# mimic1568.net
KiCad netlist of a schematic drawn in EAGLE
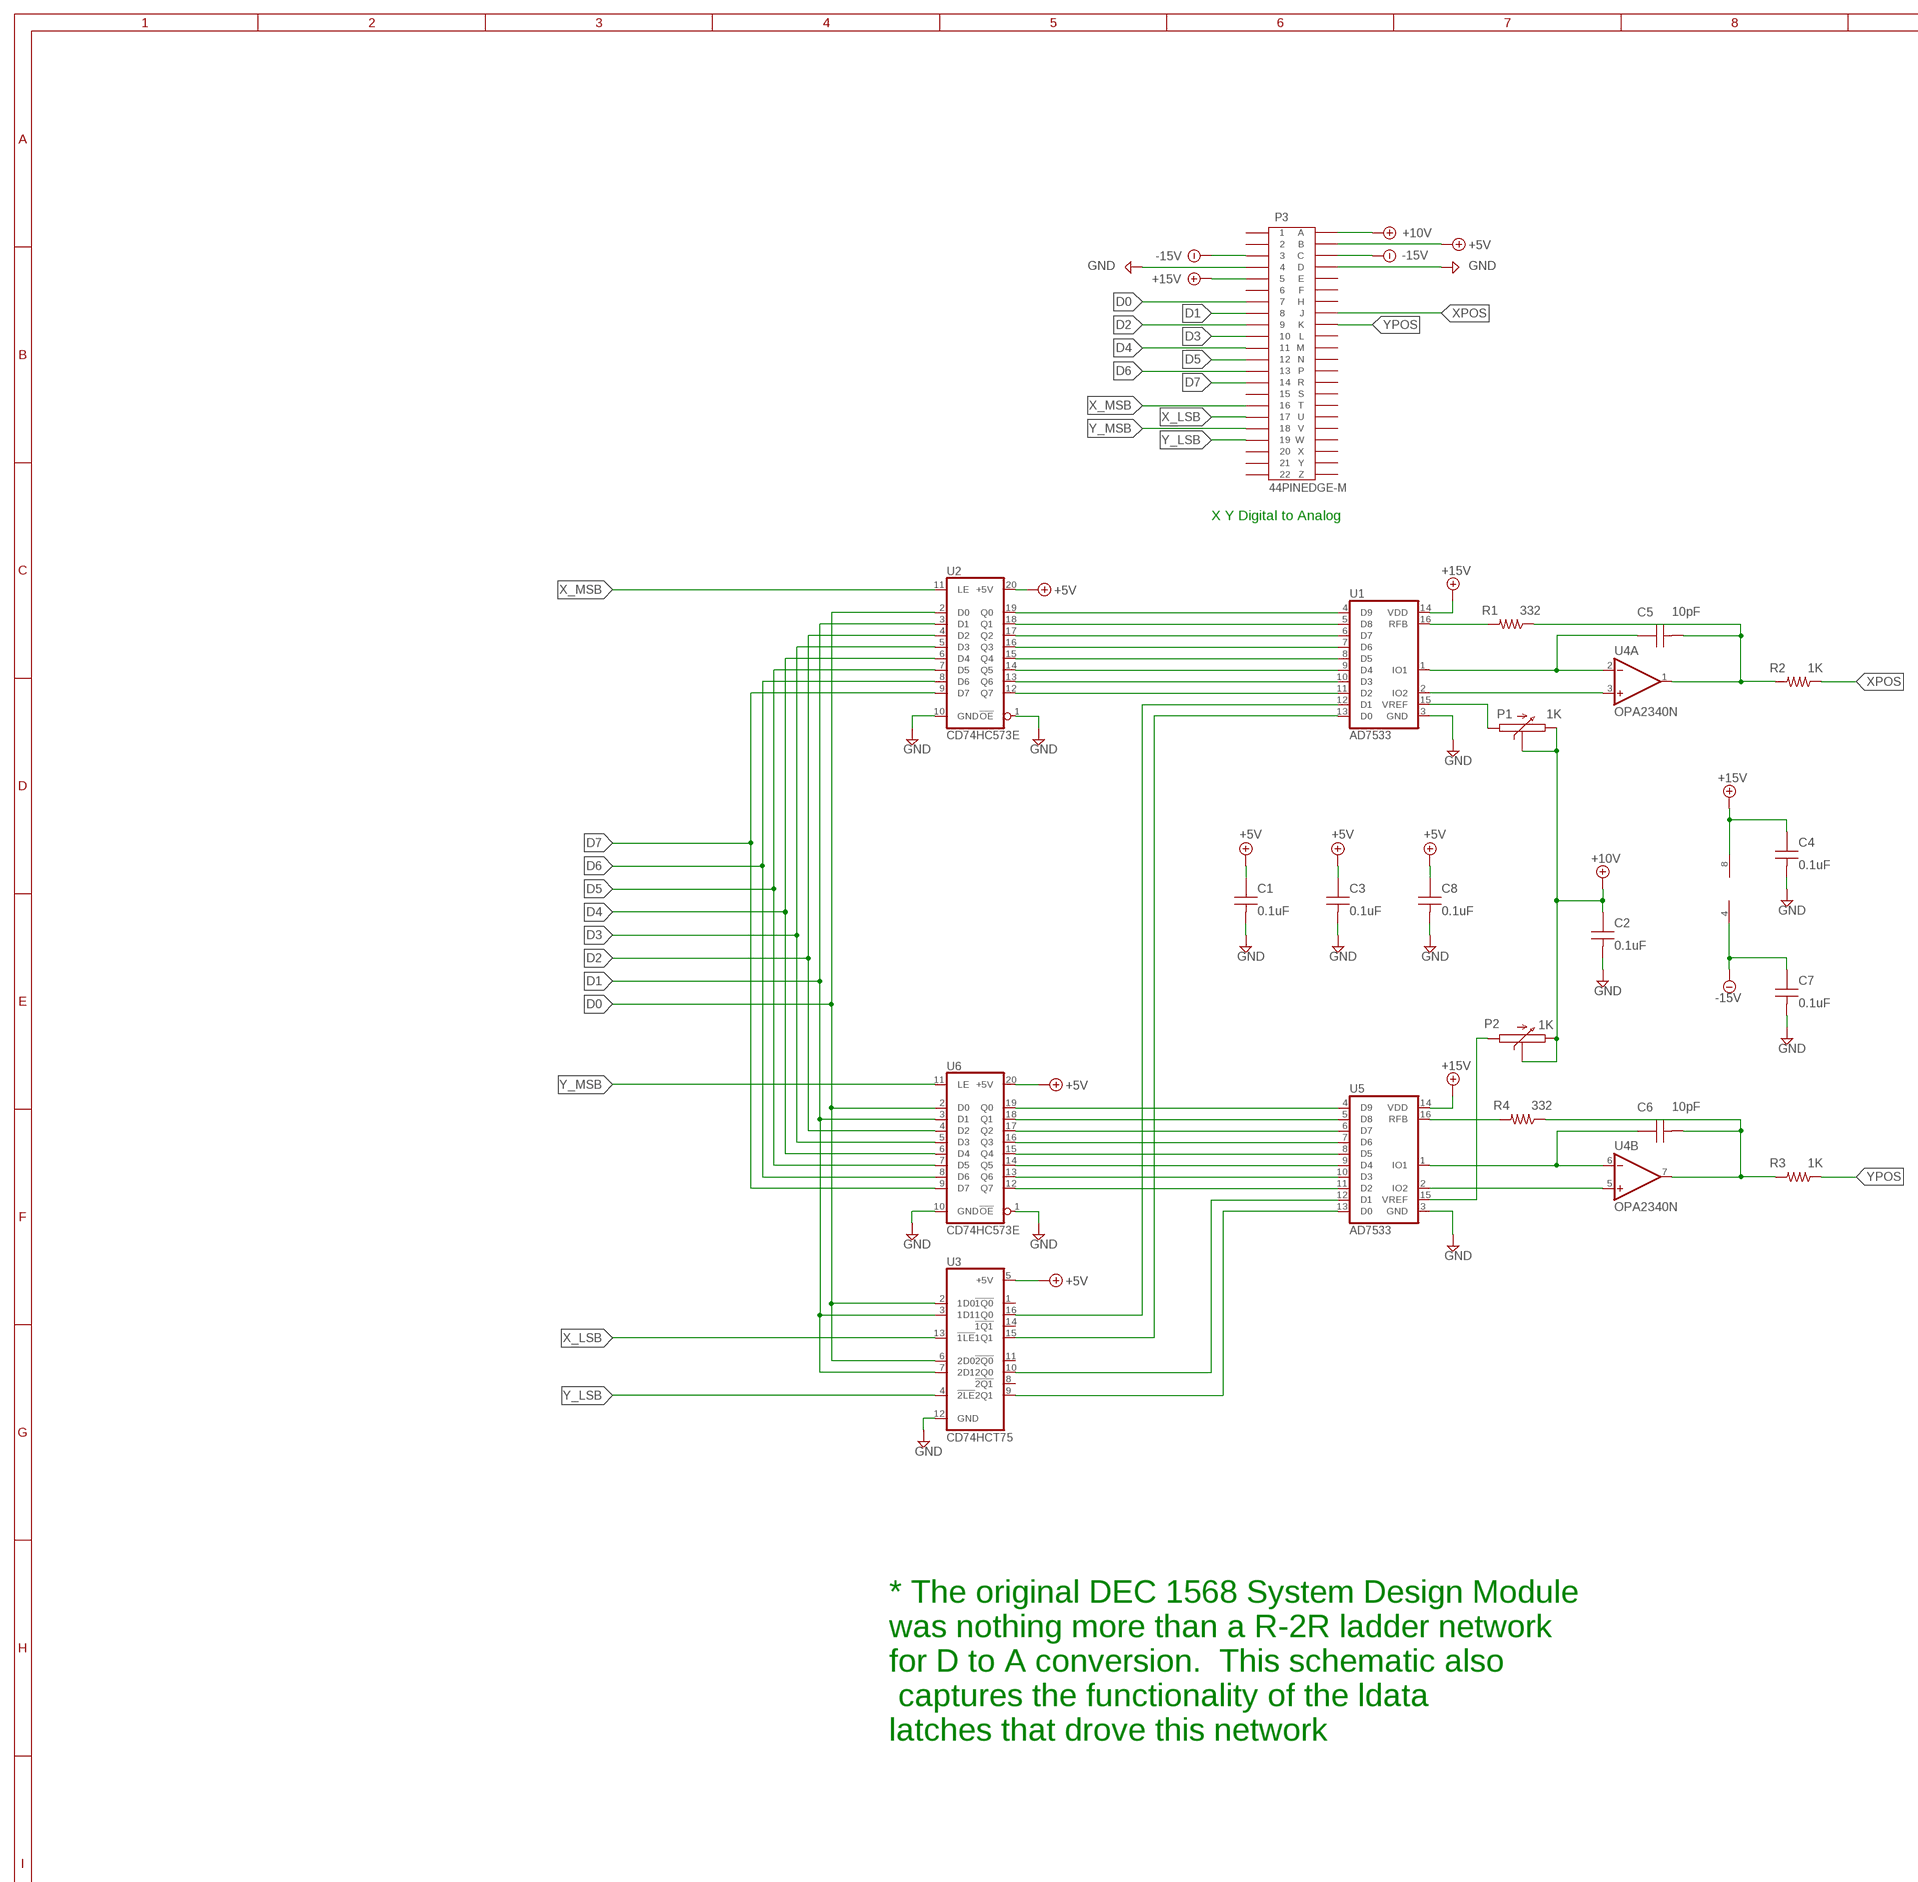
[diagram p0: schematic, sheet 1, part 1 of 2]
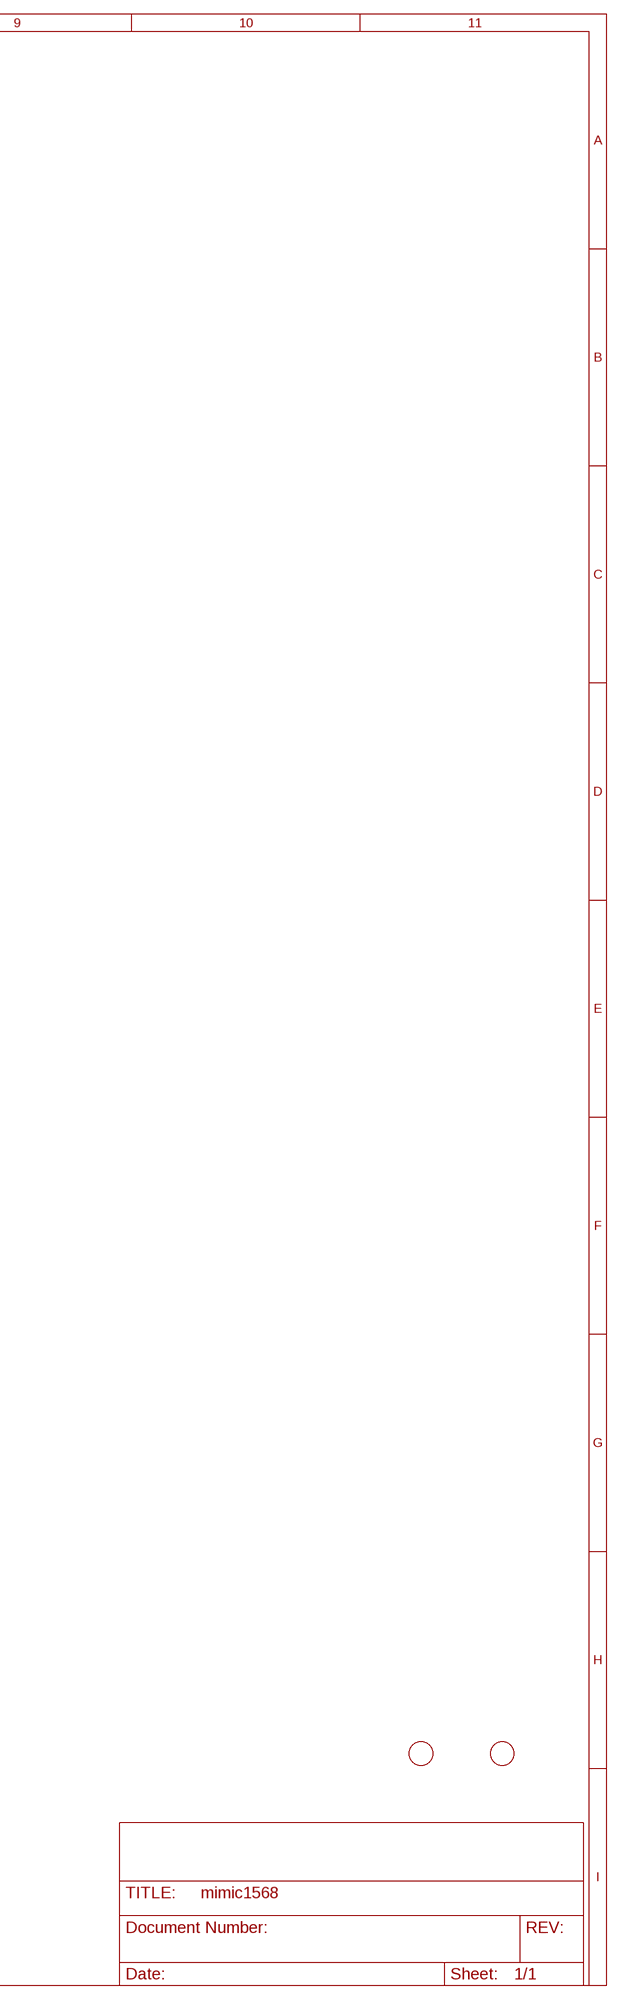
[diagram p1: schematic, sheet 1, part 2 of 2]

(export (version "E")
  (design (tool "Eeschema 10.0.6"))
  (components
    (comp (ref "C1")
      (value "0.1uF")
      (footprint "eagle-import:5MM_TH")
      (fields (field (name "MPN") "FA26X8R2A104KNU06"))
      (libsource (lib "eagle-import") (part "CAP0.1UF100V"))
    )
    (comp (ref "C2")
      (value "0.1uF")
      (footprint "eagle-import:5MM_TH")
      (fields (field (name "MPN") "FA26X8R2A104KNU06"))
      (libsource (lib "eagle-import") (part "CAP0.1UF100V"))
    )
    (comp (ref "C3")
      (value "0.1uF")
      (footprint "eagle-import:5MM_TH")
      (fields (field (name "MPN") "FA26X8R2A104KNU06"))
      (libsource (lib "eagle-import") (part "CAP0.1UF100V"))
    )
    (comp (ref "C4")
      (value "0.1uF")
      (footprint "eagle-import:5MM_TH")
      (fields (field (name "MPN") "FA26X8R2A104KNU06"))
      (libsource (lib "eagle-import") (part "CAP0.1UF100V"))
    )
    (comp (ref "C5")
      (value "10pF")
      (footprint "eagle-import:5MM_TH")
      (fields (field (name "MPN") "FA26X8R2A104KNU06"))
      (libsource (lib "eagle-import") (part "CAP0.1UF100V"))
    )
    (comp (ref "C6")
      (value "10pF")
      (footprint "eagle-import:5MM_TH")
      (fields (field (name "MPN") "FA26X8R2A104KNU06"))
      (libsource (lib "eagle-import") (part "CAP0.1UF100V"))
    )
    (comp (ref "C7")
      (value "0.1uF")
      (footprint "eagle-import:5MM_TH")
      (fields (field (name "MPN") "FA26X8R2A104KNU06"))
      (libsource (lib "eagle-import") (part "CAP0.1UF100V"))
    )
    (comp (ref "C8")
      (value "0.1uF")
      (footprint "eagle-import:5MM_TH")
      (fields (field (name "MPN") "FA26X8R2A104KNU06"))
      (libsource (lib "eagle-import") (part "CAP0.1UF100V"))
    )
    (comp (ref "P1")
      (value "1K")
      (footprint "eagle-import:3006P")
      (libsource (lib "eagle-import") (part "POT-3006P"))
    )
    (comp (ref "P2")
      (value "1K")
      (footprint "eagle-import:3006P")
      (libsource (lib "eagle-import") (part "POT-3006P"))
    )
    (comp (ref "P3")
      (value "44PINEDGE-M")
      (footprint "eagle-import:44PINEDGE")
      (libsource (lib "eagle-import") (part "44PINEDGE-M"))
    )
    (comp (ref "R1")
      (value "332")
      (footprint "eagle-import:0207_10")
      (libsource (lib "eagle-import") (part "R-1/4WATT"))
    )
    (comp (ref "R2")
      (value "1K")
      (footprint "eagle-import:0207_10")
      (libsource (lib "eagle-import") (part "R-1/4WATT"))
    )
    (comp (ref "R3")
      (value "1K")
      (footprint "eagle-import:0207_10")
      (libsource (lib "eagle-import") (part "R-1/4WATT"))
    )
    (comp (ref "R4")
      (value "332")
      (footprint "eagle-import:0207_10")
      (libsource (lib "eagle-import") (part "R-1/4WATT"))
    )
    (comp (ref "U$1")
      (value "FIDUCIAL")
      (footprint "eagle-import:FIDUCIAL_1MM")
      (libsource (lib "eagle-import") (part "FIDUCIAL"))
    )
    (comp (ref "U$2")
      (value "FIDUCIAL")
      (footprint "eagle-import:FIDUCIAL_1MM")
      (libsource (lib "eagle-import") (part "FIDUCIAL"))
    )
    (comp (ref "U1")
      (value "AD7533")
      (footprint "eagle-import:DIP-16")
      (libsource (lib "eagle-import") (part "AD7533"))
    )
    (comp (ref "U2")
      (value "CD74HC573E")
      (footprint "eagle-import:DIP-20")
      (libsource (lib "eagle-import") (part "CD74HC573E"))
    )
    (comp (ref "U3")
      (value "CD74HCT75")
      (footprint "eagle-import:DIP-16")
      (libsource (lib "eagle-import") (part "CD74HCT75"))
    )
    (comp (ref "U4")
      (value "OPA2340N")
      (footprint "eagle-import:DIP-08")
      (libsource (lib "eagle-import") (part "OPA2340N"))
    )
    (comp (ref "U5")
      (value "AD7533")
      (footprint "eagle-import:DIP-16")
      (libsource (lib "eagle-import") (part "AD7533"))
    )
    (comp (ref "U6")
      (value "CD74HC573E")
      (footprint "eagle-import:DIP-20")
      (libsource (lib "eagle-import") (part "CD74HC573E"))
    )
  )
  (nets
    (net (code "1") (name "+5V") (class "Default")
      (node (ref "C1") (pin "1") (pinfunction "1_1") (pintype "passive"))
      (node (ref "C3") (pin "1") (pinfunction "1_1") (pintype "passive"))
      (node (ref "C8") (pin "1") (pinfunction "1_1") (pintype "passive"))
      (node (ref "P3") (pin "B") (pinfunction "B_B") (pintype "passive"))
      (node (ref "U2") (pin "20") (pinfunction "+5V_20") (pintype "power_in"))
      (node (ref "U3") (pin "5") (pinfunction "+5V_5") (pintype "power_in"))
      (node (ref "U6") (pin "20") (pinfunction "+5V_20") (pintype "power_in"))
    )
    (net (code "2") (name "+10V") (class "Default")
      (node (ref "C2") (pin "1") (pinfunction "1_1") (pintype "passive"))
      (node (ref "P1") (pin "2") (pinfunction "2_2") (pintype "passive"))
      (node (ref "P1") (pin "3") (pinfunction "3_3") (pintype "passive"))
      (node (ref "P2") (pin "2") (pinfunction "2_2") (pintype "passive"))
      (node (ref "P2") (pin "3") (pinfunction "3_3") (pintype "passive"))
      (node (ref "P3") (pin "A") (pinfunction "A_A") (pintype "passive"))
    )
    (net (code "3") (name "+15V") (class "Default")
      (node (ref "C4") (pin "1") (pinfunction "1_1") (pintype "passive"))
      (node (ref "P3") (pin "5") (pinfunction "5_5") (pintype "passive"))
      (node (ref "U1") (pin "14") (pinfunction "VDD_14") (pintype "power_in"))
      (node (ref "U4") (pin "8") (pinfunction "V+_8") (pintype "power_in"))
      (node (ref "U5") (pin "14") (pinfunction "VDD_14") (pintype "power_in"))
    )
    (net (code "4") (name "-15V") (class "Default")
      (node (ref "C7") (pin "1") (pinfunction "1_1") (pintype "passive"))
      (node (ref "P3") (pin "3") (pinfunction "3_3") (pintype "passive"))
      (node (ref "P3") (pin "C") (pinfunction "C_C") (pintype "passive"))
      (node (ref "U4") (pin "4") (pinfunction "V-_4") (pintype "power_in"))
    )
    (net (code "5") (name "D0") (class "Default")
      (node (ref "P3") (pin "7") (pinfunction "7_7") (pintype "passive"))
      (node (ref "U2") (pin "2") (pinfunction "D0_2") (pintype "input"))
      (node (ref "U3") (pin "2") (pinfunction "1D0_2") (pintype "input"))
      (node (ref "U3") (pin "6") (pinfunction "2D0_6") (pintype "input"))
      (node (ref "U6") (pin "2") (pinfunction "D0_2") (pintype "input"))
    )
    (net (code "6") (name "D1") (class "Default")
      (node (ref "P3") (pin "8") (pinfunction "8_8") (pintype "passive"))
      (node (ref "U2") (pin "3") (pinfunction "D1_3") (pintype "input"))
      (node (ref "U3") (pin "3") (pinfunction "1D1_3") (pintype "input"))
      (node (ref "U3") (pin "7") (pinfunction "2D1_7") (pintype "input"))
      (node (ref "U6") (pin "3") (pinfunction "D1_3") (pintype "input"))
    )
    (net (code "7") (name "D2") (class "Default")
      (node (ref "P3") (pin "9") (pinfunction "9_9") (pintype "passive"))
      (node (ref "U2") (pin "4") (pinfunction "D2_4") (pintype "input"))
      (node (ref "U6") (pin "4") (pinfunction "D2_4") (pintype "input"))
    )
    (net (code "8") (name "D3") (class "Default")
      (node (ref "P3") (pin "10") (pinfunction "10_10") (pintype "passive"))
      (node (ref "U2") (pin "5") (pinfunction "D3_5") (pintype "input"))
      (node (ref "U6") (pin "5") (pinfunction "D3_5") (pintype "input"))
    )
    (net (code "9") (name "D4") (class "Default")
      (node (ref "P3") (pin "11") (pinfunction "11_11") (pintype "passive"))
      (node (ref "U2") (pin "6") (pinfunction "D4_6") (pintype "input"))
      (node (ref "U6") (pin "6") (pinfunction "D4_6") (pintype "input"))
    )
    (net (code "10") (name "D5") (class "Default")
      (node (ref "P3") (pin "12") (pinfunction "12_12") (pintype "passive"))
      (node (ref "U2") (pin "7") (pinfunction "D5_7") (pintype "input"))
      (node (ref "U6") (pin "7") (pinfunction "D5_7") (pintype "input"))
    )
    (net (code "11") (name "D6") (class "Default")
      (node (ref "P3") (pin "13") (pinfunction "13_13") (pintype "passive"))
      (node (ref "U2") (pin "8") (pinfunction "D6_8") (pintype "input"))
      (node (ref "U6") (pin "8") (pinfunction "D6_8") (pintype "input"))
    )
    (net (code "12") (name "D7") (class "Default")
      (node (ref "P3") (pin "14") (pinfunction "14_14") (pintype "passive"))
      (node (ref "U2") (pin "9") (pinfunction "D7_9") (pintype "input"))
      (node (ref "U6") (pin "9") (pinfunction "D7_9") (pintype "input"))
    )
    (net (code "13") (name "GND") (class "Default")
      (node (ref "C1") (pin "2") (pinfunction "2_2") (pintype "passive"))
      (node (ref "C2") (pin "2") (pinfunction "2_2") (pintype "passive"))
      (node (ref "C3") (pin "2") (pinfunction "2_2") (pintype "passive"))
      (node (ref "C4") (pin "2") (pinfunction "2_2") (pintype "passive"))
      (node (ref "C7") (pin "2") (pinfunction "2_2") (pintype "passive"))
      (node (ref "C8") (pin "2") (pinfunction "2_2") (pintype "passive"))
      (node (ref "P3") (pin "4") (pinfunction "4_4") (pintype "passive"))
      (node (ref "P3") (pin "D") (pinfunction "D_D") (pintype "passive"))
      (node (ref "U1") (pin "3") (pinfunction "GND_3") (pintype "power_in"))
      (node (ref "U2") (pin "1") (pinfunction "~{OE}_1") (pintype "input"))
      (node (ref "U2") (pin "10") (pinfunction "GND_10") (pintype "power_in"))
      (node (ref "U3") (pin "12") (pinfunction "GND_12") (pintype "power_in"))
      (node (ref "U5") (pin "3") (pinfunction "GND_3") (pintype "power_in"))
      (node (ref "U6") (pin "1") (pinfunction "~{OE}_1") (pintype "input"))
      (node (ref "U6") (pin "10") (pinfunction "GND_10") (pintype "power_in"))
    )
    (net (code "14") (name "Net-(R1-P$1)") (class "Default")
      (node (ref "C5") (pin "2") (pinfunction "2_2") (pintype "passive"))
      (node (ref "R1") (pin "1") (pinfunction "P$1_1") (pintype "passive"))
      (node (ref "R2") (pin "2") (pinfunction "P$2_2") (pintype "passive"))
      (node (ref "U4") (pin "1") (pinfunction "OUT_1") (pintype "output"))
    )
    (net (code "15") (name "Net-(R1-P$2)") (class "Default")
      (node (ref "R1") (pin "2") (pinfunction "P$2_2") (pintype "passive"))
      (node (ref "U1") (pin "16") (pinfunction "RFB_16") (pintype "input"))
    )
    (net (code "16") (name "Net-(R3-P$2)") (class "Default")
      (node (ref "C6") (pin "2") (pinfunction "2_2") (pintype "passive"))
      (node (ref "R3") (pin "2") (pinfunction "P$2_2") (pintype "passive"))
      (node (ref "R4") (pin "1") (pinfunction "P$1_1") (pintype "passive"))
      (node (ref "U4") (pin "7") (pinfunction "OUT_7") (pintype "output"))
    )
    (net (code "17") (name "Net-(R4-P$2)") (class "Default")
      (node (ref "R4") (pin "2") (pinfunction "P$2_2") (pintype "passive"))
      (node (ref "U5") (pin "16") (pinfunction "RFB_16") (pintype "input"))
    )
    (net (code "18") (name "Net-(U1-D0)") (class "Default")
      (node (ref "U1") (pin "13") (pinfunction "D0_13") (pintype "input"))
      (node (ref "U3") (pin "15") (pinfunction "1Q1_15") (pintype "output"))
    )
    (net (code "19") (name "Net-(U1-D1)") (class "Default")
      (node (ref "U1") (pin "12") (pinfunction "D1_12") (pintype "input"))
      (node (ref "U3") (pin "16") (pinfunction "1Q0_16") (pintype "output"))
    )
    (net (code "20") (name "Net-(U1-D2)") (class "Default")
      (node (ref "U1") (pin "11") (pinfunction "D2_11") (pintype "input"))
      (node (ref "U2") (pin "12") (pinfunction "Q7_12") (pintype "tri_state"))
    )
    (net (code "21") (name "Net-(U1-D3)") (class "Default")
      (node (ref "U1") (pin "10") (pinfunction "D3_10") (pintype "input"))
      (node (ref "U2") (pin "13") (pinfunction "Q6_13") (pintype "tri_state"))
    )
    (net (code "22") (name "Net-(U1-D4)") (class "Default")
      (node (ref "U1") (pin "9") (pinfunction "D4_9") (pintype "input"))
      (node (ref "U2") (pin "14") (pinfunction "Q5_14") (pintype "tri_state"))
    )
    (net (code "23") (name "Net-(U1-D5)") (class "Default")
      (node (ref "U1") (pin "8") (pinfunction "D5_8") (pintype "input"))
      (node (ref "U2") (pin "15") (pinfunction "Q4_15") (pintype "tri_state"))
    )
    (net (code "24") (name "Net-(U1-D6)") (class "Default")
      (node (ref "U1") (pin "7") (pinfunction "D6_7") (pintype "input"))
      (node (ref "U2") (pin "16") (pinfunction "Q3_16") (pintype "tri_state"))
    )
    (net (code "25") (name "Net-(U1-D7)") (class "Default")
      (node (ref "U1") (pin "6") (pinfunction "D7_6") (pintype "input"))
      (node (ref "U2") (pin "17") (pinfunction "Q2_17") (pintype "tri_state"))
    )
    (net (code "26") (name "Net-(U1-D8)") (class "Default")
      (node (ref "U1") (pin "5") (pinfunction "D8_5") (pintype "input"))
      (node (ref "U2") (pin "18") (pinfunction "Q1_18") (pintype "tri_state"))
    )
    (net (code "27") (name "Net-(U1-D9)") (class "Default")
      (node (ref "U1") (pin "4") (pinfunction "D9_4") (pintype "input"))
      (node (ref "U2") (pin "19") (pinfunction "Q0_19") (pintype "tri_state"))
    )
    (net (code "28") (name "Net-(U1-IO1)") (class "Default")
      (node (ref "C5") (pin "1") (pinfunction "1_1") (pintype "passive"))
      (node (ref "U1") (pin "1") (pinfunction "IO1_1") (pintype "output"))
      (node (ref "U4") (pin "2") (pinfunction "-IN_2") (pintype "input"))
    )
    (net (code "29") (name "Net-(U1-IO2)") (class "Default")
      (node (ref "U1") (pin "2") (pinfunction "IO2_2") (pintype "output"))
      (node (ref "U4") (pin "3") (pinfunction "+IN_3") (pintype "input"))
    )
    (net (code "30") (name "Net-(U1-VREF)") (class "Default")
      (node (ref "P1") (pin "1") (pinfunction "1_1") (pintype "passive"))
      (node (ref "U1") (pin "15") (pinfunction "VREF_15") (pintype "power_in"))
    )
    (net (code "31") (name "Net-(U3-2Q0)") (class "Default")
      (node (ref "U3") (pin "10") (pinfunction "2Q0_10") (pintype "output"))
      (node (ref "U5") (pin "12") (pinfunction "D1_12") (pintype "input"))
    )
    (net (code "32") (name "Net-(U3-2Q1)") (class "Default")
      (node (ref "U3") (pin "9") (pinfunction "2Q1_9") (pintype "output"))
      (node (ref "U5") (pin "13") (pinfunction "D0_13") (pintype "input"))
    )
    (net (code "33") (name "Net-(U4B-+IN)") (class "Default")
      (node (ref "U4") (pin "5") (pinfunction "+IN_5") (pintype "input"))
      (node (ref "U5") (pin "2") (pinfunction "IO2_2") (pintype "output"))
    )
    (net (code "34") (name "Net-(U4B--IN)") (class "Default")
      (node (ref "C6") (pin "1") (pinfunction "1_1") (pintype "passive"))
      (node (ref "U4") (pin "6") (pinfunction "-IN_6") (pintype "input"))
      (node (ref "U5") (pin "1") (pinfunction "IO1_1") (pintype "output"))
    )
    (net (code "35") (name "Net-(U5-D2)") (class "Default")
      (node (ref "U5") (pin "11") (pinfunction "D2_11") (pintype "input"))
      (node (ref "U6") (pin "12") (pinfunction "Q7_12") (pintype "tri_state"))
    )
    (net (code "36") (name "Net-(U5-D3)") (class "Default")
      (node (ref "U5") (pin "10") (pinfunction "D3_10") (pintype "input"))
      (node (ref "U6") (pin "13") (pinfunction "Q6_13") (pintype "tri_state"))
    )
    (net (code "37") (name "Net-(U5-D4)") (class "Default")
      (node (ref "U5") (pin "9") (pinfunction "D4_9") (pintype "input"))
      (node (ref "U6") (pin "14") (pinfunction "Q5_14") (pintype "tri_state"))
    )
    (net (code "38") (name "Net-(U5-D5)") (class "Default")
      (node (ref "U5") (pin "8") (pinfunction "D5_8") (pintype "input"))
      (node (ref "U6") (pin "15") (pinfunction "Q4_15") (pintype "tri_state"))
    )
    (net (code "39") (name "Net-(U5-D6)") (class "Default")
      (node (ref "U5") (pin "7") (pinfunction "D6_7") (pintype "input"))
      (node (ref "U6") (pin "16") (pinfunction "Q3_16") (pintype "tri_state"))
    )
    (net (code "40") (name "Net-(U5-D7)") (class "Default")
      (node (ref "U5") (pin "6") (pinfunction "D7_6") (pintype "input"))
      (node (ref "U6") (pin "17") (pinfunction "Q2_17") (pintype "tri_state"))
    )
    (net (code "41") (name "Net-(U5-D8)") (class "Default")
      (node (ref "U5") (pin "5") (pinfunction "D8_5") (pintype "input"))
      (node (ref "U6") (pin "18") (pinfunction "Q1_18") (pintype "tri_state"))
    )
    (net (code "42") (name "Net-(U5-D9)") (class "Default")
      (node (ref "U5") (pin "4") (pinfunction "D9_4") (pintype "input"))
      (node (ref "U6") (pin "19") (pinfunction "Q0_19") (pintype "tri_state"))
    )
    (net (code "43") (name "Net-(U5-VREF)") (class "Default")
      (node (ref "P2") (pin "1") (pinfunction "1_1") (pintype "passive"))
      (node (ref "U5") (pin "15") (pinfunction "VREF_15") (pintype "power_in"))
    )
    (net (code "44") (name "XPOS") (class "Default")
      (node (ref "P3") (pin "J") (pinfunction "J_J") (pintype "passive"))
      (node (ref "R2") (pin "1") (pinfunction "P$1_1") (pintype "passive"))
    )
    (net (code "45") (name "X_LSB") (class "Default")
      (node (ref "P3") (pin "17") (pinfunction "17_17") (pintype "passive"))
      (node (ref "U3") (pin "13") (pinfunction "~{1LE}_13") (pintype "input"))
    )
    (net (code "46") (name "X_MSB") (class "Default")
      (node (ref "P3") (pin "16") (pinfunction "16_16") (pintype "passive"))
      (node (ref "U2") (pin "11") (pinfunction "LE_11") (pintype "input"))
    )
    (net (code "47") (name "YPOS") (class "Default")
      (node (ref "P3") (pin "K") (pinfunction "K_K") (pintype "passive"))
      (node (ref "R3") (pin "1") (pinfunction "P$1_1") (pintype "passive"))
    )
    (net (code "48") (name "Y_LSB") (class "Default")
      (node (ref "P3") (pin "19") (pinfunction "19_19") (pintype "passive"))
      (node (ref "U3") (pin "4") (pinfunction "~{2LE}_4") (pintype "input"))
    )
    (net (code "49") (name "Y_MSB") (class "Default")
      (node (ref "P3") (pin "18") (pinfunction "18_18") (pintype "passive"))
      (node (ref "U6") (pin "11") (pinfunction "LE_11") (pintype "input"))
    )
    (net (code "50") (name "unconnected-(P3-Pad1)") (class "Default")
      (node (ref "P3") (pin "1") (pinfunction "1_1") (pintype "passive"))
    )
    (net (code "51") (name "unconnected-(P3-Pad2)") (class "Default")
      (node (ref "P3") (pin "2") (pinfunction "2_2") (pintype "passive"))
    )
    (net (code "52") (name "unconnected-(P3-Pad6)") (class "Default")
      (node (ref "P3") (pin "6") (pinfunction "6_6") (pintype "passive"))
    )
    (net (code "53") (name "unconnected-(P3-Pad15)") (class "Default")
      (node (ref "P3") (pin "15") (pinfunction "15_15") (pintype "passive"))
    )
    (net (code "54") (name "unconnected-(P3-Pad20)") (class "Default")
      (node (ref "P3") (pin "20") (pinfunction "20_20") (pintype "passive"))
    )
    (net (code "55") (name "unconnected-(P3-Pad21)") (class "Default")
      (node (ref "P3") (pin "21") (pinfunction "21_21") (pintype "passive"))
    )
    (net (code "56") (name "unconnected-(P3-Pad22)") (class "Default")
      (node (ref "P3") (pin "22") (pinfunction "22_22") (pintype "passive"))
    )
    (net (code "57") (name "unconnected-(P3-PadE)") (class "Default")
      (node (ref "P3") (pin "E") (pinfunction "E_E") (pintype "passive"))
    )
    (net (code "58") (name "unconnected-(P3-PadF)") (class "Default")
      (node (ref "P3") (pin "F") (pinfunction "F_F") (pintype "passive"))
    )
    (net (code "59") (name "unconnected-(P3-PadH)") (class "Default")
      (node (ref "P3") (pin "H") (pinfunction "H_H") (pintype "passive"))
    )
    (net (code "60") (name "unconnected-(P3-PadL)") (class "Default")
      (node (ref "P3") (pin "L") (pinfunction "L_L") (pintype "passive"))
    )
    (net (code "61") (name "unconnected-(P3-PadM)") (class "Default")
      (node (ref "P3") (pin "M") (pinfunction "M_M") (pintype "passive"))
    )
    (net (code "62") (name "unconnected-(P3-PadN)") (class "Default")
      (node (ref "P3") (pin "N") (pinfunction "N_N") (pintype "passive"))
    )
    (net (code "63") (name "unconnected-(P3-PadP)") (class "Default")
      (node (ref "P3") (pin "P") (pinfunction "P_P") (pintype "passive"))
    )
    (net (code "64") (name "unconnected-(P3-PadR)") (class "Default")
      (node (ref "P3") (pin "R") (pinfunction "R_R") (pintype "passive"))
    )
    (net (code "65") (name "unconnected-(P3-PadS)") (class "Default")
      (node (ref "P3") (pin "S") (pinfunction "S_S") (pintype "passive"))
    )
    (net (code "66") (name "unconnected-(P3-PadT)") (class "Default")
      (node (ref "P3") (pin "T") (pinfunction "T_T") (pintype "passive"))
    )
    (net (code "67") (name "unconnected-(P3-PadU)") (class "Default")
      (node (ref "P3") (pin "U") (pinfunction "U_U") (pintype "passive"))
    )
    (net (code "68") (name "unconnected-(P3-PadV)") (class "Default")
      (node (ref "P3") (pin "V") (pinfunction "V_V") (pintype "passive"))
    )
    (net (code "69") (name "unconnected-(P3-PadW)") (class "Default")
      (node (ref "P3") (pin "W") (pinfunction "W_W") (pintype "passive"))
    )
    (net (code "70") (name "unconnected-(P3-PadX)") (class "Default")
      (node (ref "P3") (pin "X") (pinfunction "X_X") (pintype "passive"))
    )
    (net (code "71") (name "unconnected-(P3-PadY)") (class "Default")
      (node (ref "P3") (pin "Y") (pinfunction "Y_Y") (pintype "passive"))
    )
    (net (code "72") (name "unconnected-(P3-PadZ)") (class "Default")
      (node (ref "P3") (pin "Z") (pinfunction "Z_Z") (pintype "passive"))
    )
    (net (code "73") (name "unconnected-(U3-~{1Q0}-Pad1)") (class "Default")
      (node (ref "U3") (pin "1") (pinfunction "~{1Q0}_1") (pintype "output"))
    )
    (net (code "74") (name "unconnected-(U3-~{1Q1}-Pad14)") (class "Default")
      (node (ref "U3") (pin "14") (pinfunction "~{1Q1}_14") (pintype "output"))
    )
    (net (code "75") (name "unconnected-(U3-~{2Q0}-Pad11)") (class "Default")
      (node (ref "U3") (pin "11") (pinfunction "~{2Q0}_11") (pintype "output"))
    )
    (net (code "76") (name "unconnected-(U3-~{2Q1}-Pad8)") (class "Default")
      (node (ref "U3") (pin "8") (pinfunction "~{2Q1}_8") (pintype "output"))
    )
  )
)
